# PSU_GainStage.net
KiCad netlist of a schematic drawn in EAGLE
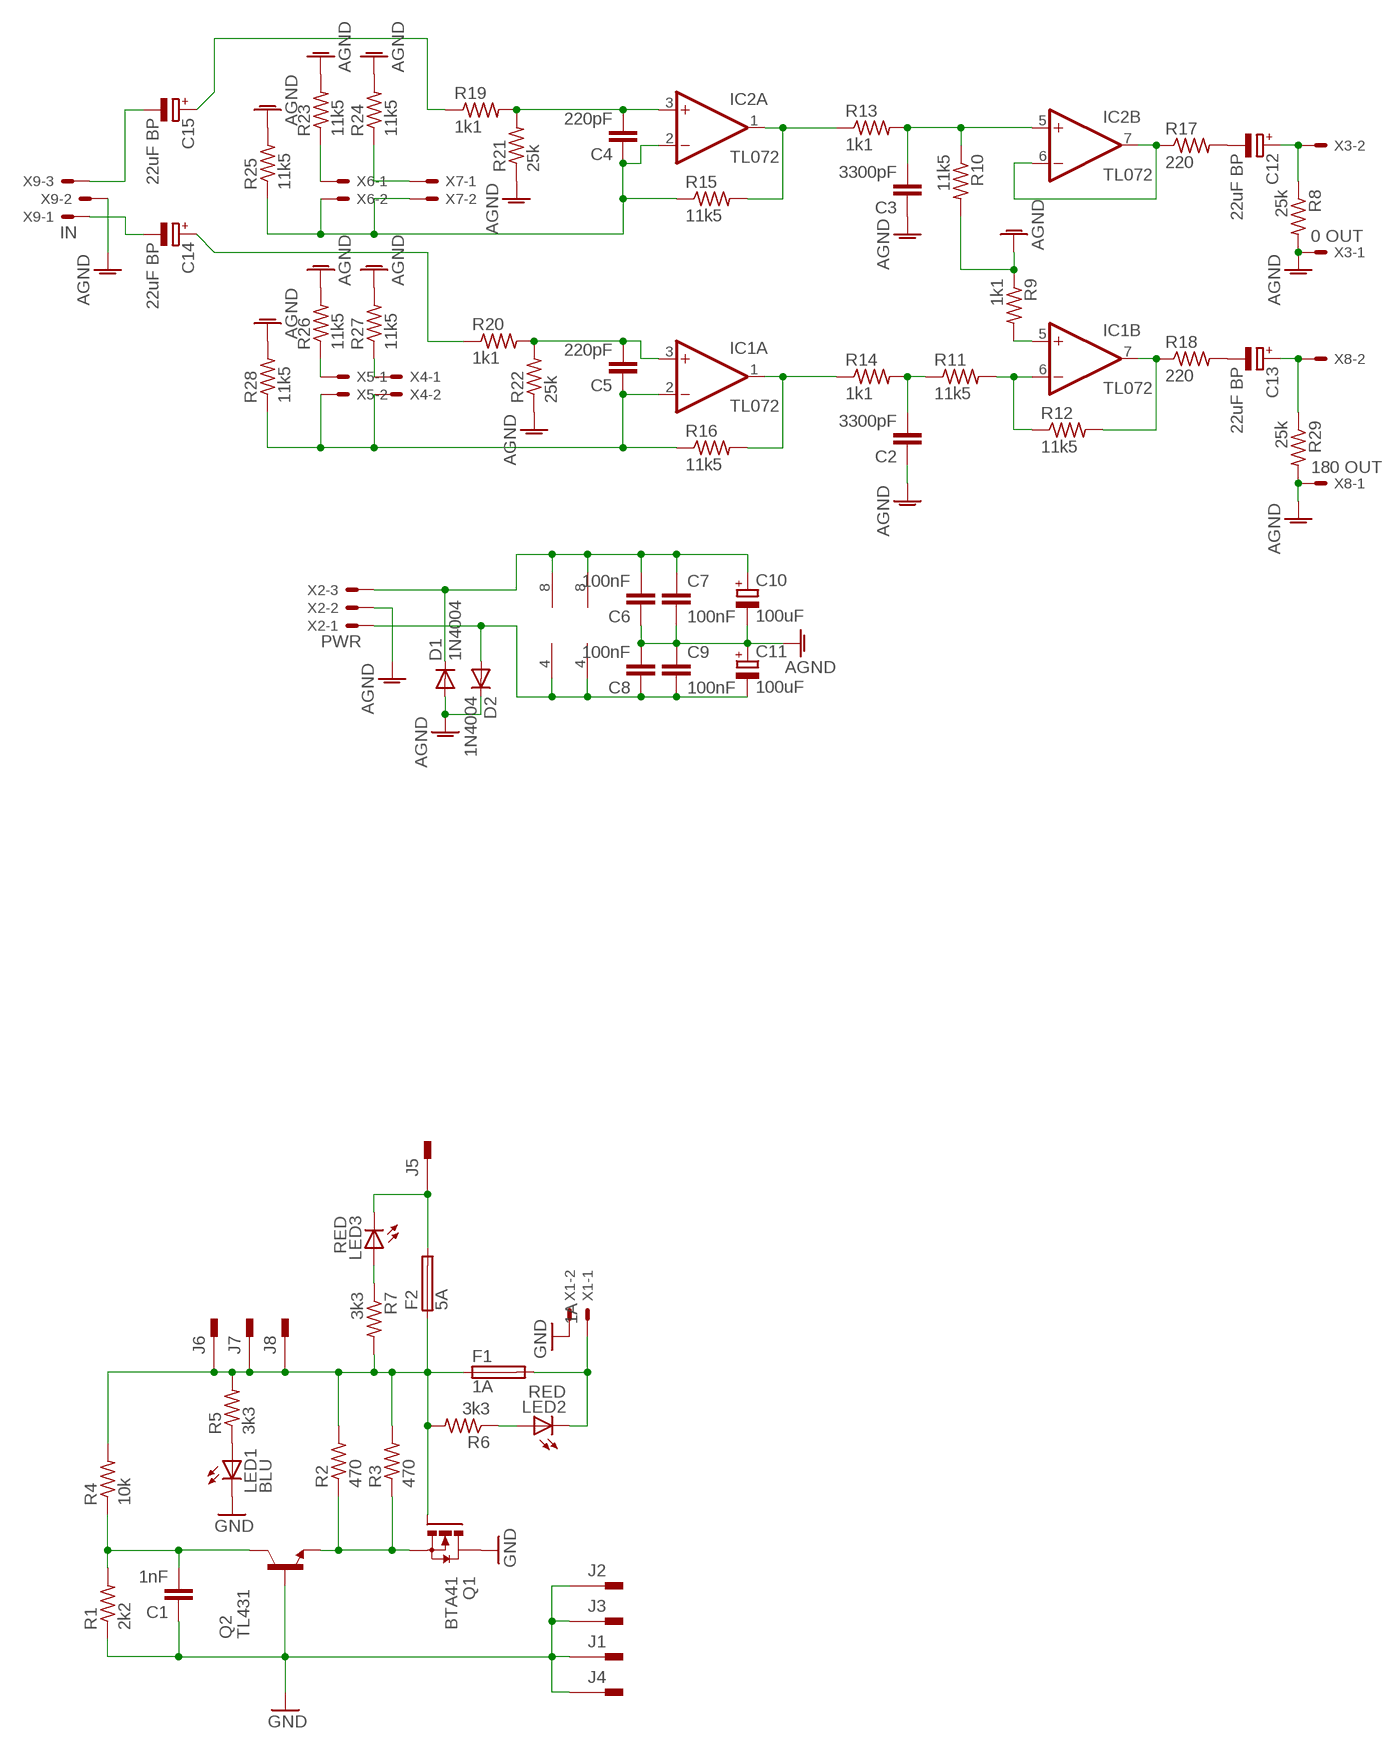
[diagram p0: schematic, sheet 1]

(export (version "E")
  (design (tool "Eeschema 10.0.6"))
  (components
    (comp (ref "C1")
      (value "1nF")
      (footprint "eagle-import:C050-035X075")
      (libsource (lib "eagle-import") (part "C-EU050-035X075"))
    )
    (comp (ref "C2")
      (value "3300pF")
      (footprint "eagle-import:C050-035X075")
      (libsource (lib "eagle-import") (part "C-EU050-035X075"))
    )
    (comp (ref "C3")
      (value "3300pF")
      (footprint "eagle-import:C050-035X075")
      (libsource (lib "eagle-import") (part "C-EU050-035X075"))
    )
    (comp (ref "C4")
      (value "220pF")
      (footprint "eagle-import:C050-035X075")
      (libsource (lib "eagle-import") (part "C-EU050-035X075"))
    )
    (comp (ref "C5")
      (value "220pF")
      (footprint "eagle-import:C050-035X075")
      (libsource (lib "eagle-import") (part "C-EU050-035X075"))
    )
    (comp (ref "C6")
      (value "100nF")
      (footprint "eagle-import:C1210")
      (libsource (lib "eagle-import") (part "C-EUC1210"))
    )
    (comp (ref "C7")
      (value "100nF")
      (footprint "eagle-import:C1210")
      (libsource (lib "eagle-import") (part "C-EUC1210"))
    )
    (comp (ref "C8")
      (value "100nF")
      (footprint "eagle-import:C1210")
      (libsource (lib "eagle-import") (part "C-EUC1210"))
    )
    (comp (ref "C9")
      (value "100nF")
      (footprint "eagle-import:C1210")
      (libsource (lib "eagle-import") (part "C-EUC1210"))
    )
    (comp (ref "C10")
      (value "100uF")
      (footprint "eagle-import:E5-8,5")
      (libsource (lib "eagle-import") (part "CPOL-EUE5-8.5"))
    )
    (comp (ref "C11")
      (value "100uF")
      (footprint "eagle-import:E5-8,5")
      (libsource (lib "eagle-import") (part "CPOL-EUE5-8.5"))
    )
    (comp (ref "C12")
      (value "22uF BP")
      (footprint "eagle-import:E3,5-10")
      (libsource (lib "eagle-import") (part "CPOL-EUE3.5-10"))
    )
    (comp (ref "C13")
      (value "22uF BP")
      (footprint "eagle-import:E3,5-10")
      (libsource (lib "eagle-import") (part "CPOL-EUE3.5-10"))
    )
    (comp (ref "C14")
      (value "22uF BP")
      (footprint "eagle-import:E3,5-10")
      (libsource (lib "eagle-import") (part "CPOL-EUE3.5-10"))
    )
    (comp (ref "C15")
      (value "22uF BP")
      (footprint "eagle-import:E3,5-10")
      (libsource (lib "eagle-import") (part "CPOL-EUE3.5-10"))
    )
    (comp (ref "D1")
      (value "1N4004")
      (footprint "eagle-import:DO41-10")
      (libsource (lib "eagle-import") (part "1N4004"))
    )
    (comp (ref "D2")
      (value "1N4004")
      (footprint "eagle-import:DO41-10")
      (libsource (lib "eagle-import") (part "1N4004"))
    )
    (comp (ref "F1")
      (value "1A")
      (footprint "eagle-import:TR5")
      (libsource (lib "eagle-import") (part "TR5"))
    )
    (comp (ref "F2")
      (value "5A")
      (footprint "eagle-import:TR5")
      (libsource (lib "eagle-import") (part "TR5"))
    )
    (comp (ref "IC1")
      (value "TL072")
      (footprint "eagle-import:DIL08")
      (libsource (lib "eagle-import") (part "1458NLM"))
    )
    (comp (ref "IC2")
      (value "TL072")
      (footprint "eagle-import:DIL08")
      (libsource (lib "eagle-import") (part "1458NLM"))
    )
    (comp (ref "J1")
      (value "PIN2F061.040")
      (footprint "eagle-import:F061.040")
      (libsource (lib "eagle-import") (part "PIN2F061.040"))
    )
    (comp (ref "J2")
      (value "PIN2F061.040")
      (footprint "eagle-import:F061.040")
      (libsource (lib "eagle-import") (part "PIN2F061.040"))
    )
    (comp (ref "J3")
      (value "PIN2F061.040")
      (footprint "eagle-import:F061.040")
      (libsource (lib "eagle-import") (part "PIN2F061.040"))
    )
    (comp (ref "J4")
      (value "PIN2F061.040")
      (footprint "eagle-import:F061.040")
      (libsource (lib "eagle-import") (part "PIN2F061.040"))
    )
    (comp (ref "J5")
      (value "PIN2F061.040")
      (footprint "eagle-import:F061.040")
      (libsource (lib "eagle-import") (part "PIN2F061.040"))
    )
    (comp (ref "J6")
      (value "PIN2F061.040")
      (footprint "eagle-import:F061.040")
      (libsource (lib "eagle-import") (part "PIN2F061.040"))
    )
    (comp (ref "J7")
      (value "PIN2F061.040")
      (footprint "eagle-import:F061.040")
      (libsource (lib "eagle-import") (part "PIN2F061.040"))
    )
    (comp (ref "J8")
      (value "PIN2F061.040")
      (footprint "eagle-import:F061.040")
      (libsource (lib "eagle-import") (part "PIN2F061.040"))
    )
    (comp (ref "LED1")
      (value "BLU")
      (footprint "eagle-import:LED5MM")
      (libsource (lib "eagle-import") (part "LED5MM"))
    )
    (comp (ref "LED2")
      (value "RED")
      (footprint "eagle-import:LED5MM")
      (libsource (lib "eagle-import") (part "LED5MM"))
    )
    (comp (ref "LED3")
      (value "RED")
      (footprint "eagle-import:LED5MM")
      (libsource (lib "eagle-import") (part "LED5MM"))
    )
    (comp (ref "Q1")
      (value "BTA41")
      (footprint "eagle-import:TO247BV")
      (libsource (lib "eagle-import") (part "IRFP240"))
    )
    (comp (ref "Q2")
      (value "TL431")
      (footprint "eagle-import:TO92-EBC")
      (libsource (lib "eagle-import") (part "BC449"))
    )
    (comp (ref "R1")
      (value "2k2")
      (footprint "eagle-import:0309_12")
      (libsource (lib "eagle-import") (part "R-US_0309/12"))
    )
    (comp (ref "R2")
      (value "470")
      (footprint "eagle-import:0411_15")
      (libsource (lib "eagle-import") (part "R-US_0411/15"))
    )
    (comp (ref "R3")
      (value "470")
      (footprint "eagle-import:0411_15")
      (libsource (lib "eagle-import") (part "R-US_0411/15"))
    )
    (comp (ref "R4")
      (value "10k")
      (footprint "eagle-import:0309_12")
      (libsource (lib "eagle-import") (part "R-US_0309/12"))
    )
    (comp (ref "R5")
      (value "3k3")
      (footprint "eagle-import:0309_12")
      (libsource (lib "eagle-import") (part "R-US_0309/12"))
    )
    (comp (ref "R6")
      (value "3k3")
      (footprint "eagle-import:0309_12")
      (libsource (lib "eagle-import") (part "R-US_0309/12"))
    )
    (comp (ref "R7")
      (value "3k3")
      (footprint "eagle-import:0309_12")
      (libsource (lib "eagle-import") (part "R-US_0309/12"))
    )
    (comp (ref "R8")
      (value "25k")
      (footprint "eagle-import:0309_12")
      (libsource (lib "eagle-import") (part "R-US_0309/12"))
    )
    (comp (ref "R9")
      (value "1k1")
      (footprint "eagle-import:0309_12")
      (libsource (lib "eagle-import") (part "R-US_0309/12"))
    )
    (comp (ref "R10")
      (value "11k5")
      (footprint "eagle-import:0309_12")
      (libsource (lib "eagle-import") (part "R-US_0309/12"))
    )
    (comp (ref "R11")
      (value "11k5")
      (footprint "eagle-import:0309_10")
      (libsource (lib "eagle-import") (part "R-US_0309/10"))
    )
    (comp (ref "R12")
      (value "11k5")
      (footprint "eagle-import:0309_10")
      (libsource (lib "eagle-import") (part "R-US_0309/10"))
    )
    (comp (ref "R13")
      (value "1k1")
      (footprint "eagle-import:0309_12")
      (libsource (lib "eagle-import") (part "R-US_0309/12"))
    )
    (comp (ref "R14")
      (value "1k1")
      (footprint "eagle-import:0309_12")
      (libsource (lib "eagle-import") (part "R-US_0309/12"))
    )
    (comp (ref "R15")
      (value "11k5")
      (footprint "eagle-import:0309_10")
      (libsource (lib "eagle-import") (part "R-US_0309/10"))
    )
    (comp (ref "R16")
      (value "11k5")
      (footprint "eagle-import:0309_10")
      (libsource (lib "eagle-import") (part "R-US_0309/10"))
    )
    (comp (ref "R17")
      (value "220")
      (footprint "eagle-import:0309_12")
      (libsource (lib "eagle-import") (part "R-US_0309/12"))
    )
    (comp (ref "R18")
      (value "220")
      (footprint "eagle-import:0309_10")
      (libsource (lib "eagle-import") (part "R-US_0309/10"))
    )
    (comp (ref "R19")
      (value "1k1")
      (footprint "eagle-import:0309_12")
      (libsource (lib "eagle-import") (part "R-US_0309/12"))
    )
    (comp (ref "R20")
      (value "1k1")
      (footprint "eagle-import:0309_10")
      (libsource (lib "eagle-import") (part "R-US_0309/10"))
    )
    (comp (ref "R21")
      (value "25k")
      (footprint "eagle-import:0309_10")
      (libsource (lib "eagle-import") (part "R-US_0309/10"))
    )
    (comp (ref "R22")
      (value "25k")
      (footprint "eagle-import:0309_10")
      (libsource (lib "eagle-import") (part "R-US_0309/10"))
    )
    (comp (ref "R23")
      (value "11k5")
      (footprint "eagle-import:0309_10")
      (libsource (lib "eagle-import") (part "R-US_0309/10"))
    )
    (comp (ref "R24")
      (value "11k5")
      (footprint "eagle-import:0309_10")
      (libsource (lib "eagle-import") (part "R-US_0309/10"))
    )
    (comp (ref "R25")
      (value "11k5")
      (footprint "eagle-import:0309_10")
      (libsource (lib "eagle-import") (part "R-US_0309/10"))
    )
    (comp (ref "R26")
      (value "11k5")
      (footprint "eagle-import:0309_10")
      (libsource (lib "eagle-import") (part "R-US_0309/10"))
    )
    (comp (ref "R27")
      (value "11k5")
      (footprint "eagle-import:0309_10")
      (libsource (lib "eagle-import") (part "R-US_0309/10"))
    )
    (comp (ref "R28")
      (value "11k5")
      (footprint "eagle-import:0309_10")
      (libsource (lib "eagle-import") (part "R-US_0309/10"))
    )
    (comp (ref "R29")
      (value "25k")
      (footprint "eagle-import:0309_12")
      (libsource (lib "eagle-import") (part "R-US_0309/12"))
    )
    (comp (ref "X1")
      (value "1A")
      (footprint "eagle-import:22-23-2021")
      (fields (field (name "MF") "MOLEX") (field (name "MPN") "22-23-2021"))
      (libsource (lib "eagle-import") (part "22-23-2021"))
    )
    (comp (ref "X2")
      (value "PWR")
      (footprint "eagle-import:22-23-2031")
      (fields (field (name "MF") "MOLEX") (field (name "MPN") "22-23-2031"))
      (libsource (lib "eagle-import") (part "22-23-2031"))
    )
    (comp (ref "X3")
      (value "0 OUT")
      (footprint "eagle-import:22-23-2021")
      (fields (field (name "MF") "MOLEX") (field (name "MPN") "22-23-2021"))
      (libsource (lib "eagle-import") (part "22-23-2021"))
    )
    (comp (ref "X4")
      (value "22-23-2021")
      (footprint "eagle-import:22-23-2021")
      (fields (field (name "MF") "MOLEX"))
      (libsource (lib "eagle-import") (part "22-23-2021"))
    )
    (comp (ref "X5")
      (value "22-23-2021")
      (footprint "eagle-import:22-23-2021")
      (fields (field (name "MF") "MOLEX"))
      (libsource (lib "eagle-import") (part "22-23-2021"))
    )
    (comp (ref "X6")
      (value "22-23-2021")
      (footprint "eagle-import:22-23-2021")
      (fields (field (name "MF") "MOLEX"))
      (libsource (lib "eagle-import") (part "22-23-2021"))
    )
    (comp (ref "X7")
      (value "22-23-2021")
      (footprint "eagle-import:22-23-2021")
      (fields (field (name "MF") "MOLEX"))
      (libsource (lib "eagle-import") (part "22-23-2021"))
    )
    (comp (ref "X8")
      (value "180 OUT")
      (footprint "eagle-import:22-23-2021")
      (fields (field (name "MF") "MOLEX") (field (name "MPN") "22-23-2021"))
      (libsource (lib "eagle-import") (part "22-23-2021"))
    )
    (comp (ref "X9")
      (value "IN")
      (footprint "eagle-import:22-23-2031")
      (fields (field (name "MF") "MOLEX") (field (name "MPN") "22-23-2031"))
      (libsource (lib "eagle-import") (part "22-23-2031"))
    )
  )
  (nets
    (net (code "1") (name "AGND") (class "Default")
      (node (ref "C10") (pin "-") (pinfunction "-_-") (pintype "passive"))
      (node (ref "C11") (pin "+") (pinfunction "+_+") (pintype "passive"))
      (node (ref "C2") (pin "1") (pinfunction "1_1") (pintype "passive"))
      (node (ref "C3") (pin "1") (pinfunction "1_1") (pintype "passive"))
      (node (ref "C6") (pin "1") (pinfunction "1_1") (pintype "passive"))
      (node (ref "C7") (pin "2") (pinfunction "2_2") (pintype "passive"))
      (node (ref "C8") (pin "2") (pinfunction "2_2") (pintype "passive"))
      (node (ref "C9") (pin "1") (pinfunction "1_1") (pintype "passive"))
      (node (ref "D1") (pin "A") (pinfunction "A_A") (pintype "passive"))
      (node (ref "D2") (pin "C") (pinfunction "C_C") (pintype "passive"))
      (node (ref "R10") (pin "2") (pinfunction "2_2") (pintype "passive"))
      (node (ref "R21") (pin "1") (pinfunction "1_1") (pintype "passive"))
      (node (ref "R22") (pin "1") (pinfunction "1_1") (pintype "passive"))
      (node (ref "R23") (pin "2") (pinfunction "2_2") (pintype "passive"))
      (node (ref "R24") (pin "2") (pinfunction "2_2") (pintype "passive"))
      (node (ref "R25") (pin "2") (pinfunction "2_2") (pintype "passive"))
      (node (ref "R26") (pin "2") (pinfunction "2_2") (pintype "passive"))
      (node (ref "R27") (pin "2") (pinfunction "2_2") (pintype "passive"))
      (node (ref "R28") (pin "2") (pinfunction "2_2") (pintype "passive"))
      (node (ref "R29") (pin "2") (pinfunction "2_2") (pintype "passive"))
      (node (ref "R8") (pin "2") (pinfunction "2_2") (pintype "passive"))
      (node (ref "R9") (pin "1") (pinfunction "1_1") (pintype "passive"))
      (node (ref "X2") (pin "2") (pinfunction "S_2") (pintype "passive"))
      (node (ref "X3") (pin "1") (pinfunction "S_1") (pintype "passive"))
      (node (ref "X8") (pin "1") (pinfunction "S_1") (pintype "passive"))
      (node (ref "X9") (pin "2") (pinfunction "S_2") (pintype "passive"))
    )
    (net (code "2") (name "GND") (class "Default")
      (node (ref "C1") (pin "1") (pinfunction "1_1") (pintype "passive"))
      (node (ref "J1") (pin "A1") (pinfunction "1_A1") (pintype "passive"))
      (node (ref "J1") (pin "A2") (pinfunction "1_A2") (pintype "passive"))
      (node (ref "J2") (pin "A1") (pinfunction "1_A1") (pintype "passive"))
      (node (ref "J2") (pin "A2") (pinfunction "1_A2") (pintype "passive"))
      (node (ref "J3") (pin "A1") (pinfunction "1_A1") (pintype "passive"))
      (node (ref "J3") (pin "A2") (pinfunction "1_A2") (pintype "passive"))
      (node (ref "J4") (pin "A1") (pinfunction "1_A1") (pintype "passive"))
      (node (ref "J4") (pin "A2") (pinfunction "1_A2") (pintype "passive"))
      (node (ref "LED1") (pin "K") (pinfunction "C_K") (pintype "passive"))
      (node (ref "Q1") (pin "D") (pinfunction "D_D") (pintype "passive"))
      (node (ref "Q2") (pin "B") (pinfunction "B_B") (pintype "passive"))
      (node (ref "R1") (pin "1") (pinfunction "1_1") (pintype "passive"))
      (node (ref "X1") (pin "2") (pinfunction "S_2") (pintype "passive"))
    )
    (net (code "3") (name "Net-(C1-Pad2)") (class "Default")
      (node (ref "C1") (pin "2") (pinfunction "2_2") (pintype "passive"))
      (node (ref "Q2") (pin "C") (pinfunction "C_C") (pintype "passive"))
      (node (ref "R1") (pin "2") (pinfunction "2_2") (pintype "passive"))
      (node (ref "R4") (pin "1") (pinfunction "1_1") (pintype "passive"))
    )
    (net (code "4") (name "Net-(C2-Pad2)") (class "Default")
      (node (ref "C2") (pin "2") (pinfunction "2_2") (pintype "passive"))
      (node (ref "R11") (pin "1") (pinfunction "1_1") (pintype "passive"))
      (node (ref "R14") (pin "2") (pinfunction "2_2") (pintype "passive"))
    )
    (net (code "5") (name "Net-(C12-Pad-)") (class "Default")
      (node (ref "C12") (pin "-") (pinfunction "-_-") (pintype "passive"))
      (node (ref "R17") (pin "2") (pinfunction "2_2") (pintype "passive"))
    )
    (net (code "6") (name "Net-(C13-Pad-)") (class "Default")
      (node (ref "C13") (pin "-") (pinfunction "-_-") (pintype "passive"))
      (node (ref "R18") (pin "2") (pinfunction "2_2") (pintype "passive"))
    )
    (net (code "7") (name "Net-(C14-Pad+)") (class "Default")
      (node (ref "C14") (pin "+") (pinfunction "+_+") (pintype "passive"))
      (node (ref "R20") (pin "1") (pinfunction "1_1") (pintype "passive"))
    )
    (net (code "8") (name "Net-(C15-Pad+)") (class "Default")
      (node (ref "C15") (pin "+") (pinfunction "+_+") (pintype "passive"))
      (node (ref "R19") (pin "1") (pinfunction "1_1") (pintype "passive"))
    )
    (net (code "9") (name "Net-(F1-Pad1)") (class "Default")
      (node (ref "F1") (pin "1") (pinfunction "1_1") (pintype "passive"))
      (node (ref "F2") (pin "1") (pinfunction "1_1") (pintype "passive"))
      (node (ref "J6") (pin "A1") (pinfunction "1_A1") (pintype "passive"))
      (node (ref "J6") (pin "A2") (pinfunction "1_A2") (pintype "passive"))
      (node (ref "J7") (pin "A1") (pinfunction "1_A1") (pintype "passive"))
      (node (ref "J7") (pin "A2") (pinfunction "1_A2") (pintype "passive"))
      (node (ref "J8") (pin "A1") (pinfunction "1_A1") (pintype "passive"))
      (node (ref "J8") (pin "A2") (pinfunction "1_A2") (pintype "passive"))
      (node (ref "Q1") (pin "G") (pinfunction "G_G") (pintype "passive"))
      (node (ref "R2") (pin "2") (pinfunction "2_2") (pintype "passive"))
      (node (ref "R3") (pin "2") (pinfunction "2_2") (pintype "passive"))
      (node (ref "R4") (pin "2") (pinfunction "2_2") (pintype "passive"))
      (node (ref "R5") (pin "2") (pinfunction "2_2") (pintype "passive"))
      (node (ref "R6") (pin "2") (pinfunction "2_2") (pintype "passive"))
      (node (ref "R7") (pin "2") (pinfunction "2_2") (pintype "passive"))
    )
    (net (code "10") (name "Net-(IC1A-+IN)") (class "Default")
      (node (ref "C5") (pin "2") (pinfunction "2_2") (pintype "passive"))
      (node (ref "IC1") (pin "3") (pinfunction "+IN_3") (pintype "input"))
      (node (ref "R20") (pin "2") (pinfunction "2_2") (pintype "passive"))
      (node (ref "R22") (pin "2") (pinfunction "2_2") (pintype "passive"))
    )
    (net (code "11") (name "Net-(IC1A--IN)") (class "Default")
      (node (ref "C5") (pin "1") (pinfunction "1_1") (pintype "passive"))
      (node (ref "IC1") (pin "2") (pinfunction "-IN_2") (pintype "input"))
      (node (ref "R16") (pin "1") (pinfunction "1_1") (pintype "passive"))
      (node (ref "R28") (pin "1") (pinfunction "1_1") (pintype "passive"))
      (node (ref "X4") (pin "2") (pinfunction "S_2") (pintype "passive"))
      (node (ref "X5") (pin "2") (pinfunction "S_2") (pintype "passive"))
    )
    (net (code "12") (name "Net-(IC1A-OUT)") (class "Default")
      (node (ref "IC1") (pin "1") (pinfunction "OUT_1") (pintype "output"))
      (node (ref "R14") (pin "1") (pinfunction "1_1") (pintype "passive"))
      (node (ref "R16") (pin "2") (pinfunction "2_2") (pintype "passive"))
    )
    (net (code "13") (name "Net-(IC1B-+IN)") (class "Default")
      (node (ref "IC1") (pin "5") (pinfunction "+IN_5") (pintype "input"))
      (node (ref "R9") (pin "2") (pinfunction "2_2") (pintype "passive"))
    )
    (net (code "14") (name "Net-(IC1B--IN)") (class "Default")
      (node (ref "IC1") (pin "6") (pinfunction "-IN_6") (pintype "input"))
      (node (ref "R11") (pin "2") (pinfunction "2_2") (pintype "passive"))
      (node (ref "R12") (pin "1") (pinfunction "1_1") (pintype "passive"))
    )
    (net (code "15") (name "Net-(IC1B-OUT)") (class "Default")
      (node (ref "IC1") (pin "7") (pinfunction "OUT_7") (pintype "output"))
      (node (ref "R12") (pin "2") (pinfunction "2_2") (pintype "passive"))
      (node (ref "R18") (pin "1") (pinfunction "1_1") (pintype "passive"))
    )
    (net (code "16") (name "Net-(IC1C-V+)") (class "Default")
      (node (ref "C10") (pin "+") (pinfunction "+_+") (pintype "passive"))
      (node (ref "C6") (pin "2") (pinfunction "2_2") (pintype "passive"))
      (node (ref "C7") (pin "1") (pinfunction "1_1") (pintype "passive"))
      (node (ref "D1") (pin "C") (pinfunction "C_C") (pintype "passive"))
      (node (ref "IC1") (pin "8") (pinfunction "V+_8") (pintype "power_in"))
      (node (ref "IC2") (pin "8") (pinfunction "V+_8") (pintype "power_in"))
      (node (ref "X2") (pin "3") (pinfunction "S_3") (pintype "passive"))
    )
    (net (code "17") (name "Net-(IC1C-V-)") (class "Default")
      (node (ref "C11") (pin "-") (pinfunction "-_-") (pintype "passive"))
      (node (ref "C8") (pin "1") (pinfunction "1_1") (pintype "passive"))
      (node (ref "C9") (pin "2") (pinfunction "2_2") (pintype "passive"))
      (node (ref "D2") (pin "A") (pinfunction "A_A") (pintype "passive"))
      (node (ref "IC1") (pin "4") (pinfunction "V-_4") (pintype "power_in"))
      (node (ref "IC2") (pin "4") (pinfunction "V-_4") (pintype "power_in"))
      (node (ref "X2") (pin "1") (pinfunction "S_1") (pintype "passive"))
    )
    (net (code "18") (name "Net-(IC2A-+IN)") (class "Default")
      (node (ref "C4") (pin "2") (pinfunction "2_2") (pintype "passive"))
      (node (ref "IC2") (pin "3") (pinfunction "+IN_3") (pintype "input"))
      (node (ref "R19") (pin "2") (pinfunction "2_2") (pintype "passive"))
      (node (ref "R21") (pin "2") (pinfunction "2_2") (pintype "passive"))
    )
    (net (code "19") (name "Net-(IC2A--IN)") (class "Default")
      (node (ref "C4") (pin "1") (pinfunction "1_1") (pintype "passive"))
      (node (ref "IC2") (pin "2") (pinfunction "-IN_2") (pintype "input"))
      (node (ref "R15") (pin "1") (pinfunction "1_1") (pintype "passive"))
      (node (ref "R25") (pin "1") (pinfunction "1_1") (pintype "passive"))
      (node (ref "X6") (pin "2") (pinfunction "S_2") (pintype "passive"))
      (node (ref "X7") (pin "2") (pinfunction "S_2") (pintype "passive"))
    )
    (net (code "20") (name "Net-(IC2A-OUT)") (class "Default")
      (node (ref "IC2") (pin "1") (pinfunction "OUT_1") (pintype "output"))
      (node (ref "R13") (pin "1") (pinfunction "1_1") (pintype "passive"))
      (node (ref "R15") (pin "2") (pinfunction "2_2") (pintype "passive"))
    )
    (net (code "21") (name "Net-(IC2B-+IN)") (class "Default")
      (node (ref "C3") (pin "2") (pinfunction "2_2") (pintype "passive"))
      (node (ref "IC2") (pin "5") (pinfunction "+IN_5") (pintype "input"))
      (node (ref "R10") (pin "1") (pinfunction "1_1") (pintype "passive"))
      (node (ref "R13") (pin "2") (pinfunction "2_2") (pintype "passive"))
    )
    (net (code "22") (name "Net-(IC2B--IN)") (class "Default")
      (node (ref "IC2") (pin "6") (pinfunction "-IN_6") (pintype "input"))
      (node (ref "IC2") (pin "7") (pinfunction "OUT_7") (pintype "output"))
      (node (ref "R17") (pin "1") (pinfunction "1_1") (pintype "passive"))
    )
    (net (code "23") (name "Net-(LED1-PadA)") (class "Default")
      (node (ref "LED1") (pin "A") (pinfunction "A_A") (pintype "passive"))
      (node (ref "R5") (pin "1") (pinfunction "1_1") (pintype "passive"))
    )
    (net (code "24") (name "Net-(LED2-C)") (class "Default")
      (node (ref "F1") (pin "2") (pinfunction "2_2") (pintype "passive"))
      (node (ref "LED2") (pin "K") (pinfunction "C_K") (pintype "passive"))
      (node (ref "X1") (pin "1") (pinfunction "S_1") (pintype "passive"))
    )
    (net (code "25") (name "Net-(LED2-PadA)") (class "Default")
      (node (ref "LED2") (pin "A") (pinfunction "A_A") (pintype "passive"))
      (node (ref "R6") (pin "1") (pinfunction "1_1") (pintype "passive"))
    )
    (net (code "26") (name "Net-(LED3-C)") (class "Default")
      (node (ref "F2") (pin "2") (pinfunction "2_2") (pintype "passive"))
      (node (ref "J5") (pin "A1") (pinfunction "1_A1") (pintype "passive"))
      (node (ref "J5") (pin "A2") (pinfunction "1_A2") (pintype "passive"))
      (node (ref "LED3") (pin "K") (pinfunction "C_K") (pintype "passive"))
    )
    (net (code "27") (name "Net-(LED3-PadA)") (class "Default")
      (node (ref "LED3") (pin "A") (pinfunction "A_A") (pintype "passive"))
      (node (ref "R7") (pin "1") (pinfunction "1_1") (pintype "passive"))
    )
    (net (code "28") (name "Net-(Q1-PadS)") (class "Default")
      (node (ref "Q1") (pin "S") (pinfunction "S_S") (pintype "passive"))
      (node (ref "Q2") (pin "E") (pinfunction "E_E") (pintype "passive"))
      (node (ref "R2") (pin "1") (pinfunction "1_1") (pintype "passive"))
      (node (ref "R3") (pin "1") (pinfunction "1_1") (pintype "passive"))
    )
    (net (code "29") (name "Net-(X3B-S)") (class "Default")
      (node (ref "C12") (pin "+") (pinfunction "+_+") (pintype "passive"))
      (node (ref "R8") (pin "1") (pinfunction "1_1") (pintype "passive"))
      (node (ref "X3") (pin "2") (pinfunction "S_2") (pintype "passive"))
    )
    (net (code "30") (name "Net-(X4A-S)") (class "Default")
      (node (ref "R27") (pin "1") (pinfunction "1_1") (pintype "passive"))
      (node (ref "X4") (pin "1") (pinfunction "S_1") (pintype "passive"))
    )
    (net (code "31") (name "Net-(X5A-S)") (class "Default")
      (node (ref "R26") (pin "1") (pinfunction "1_1") (pintype "passive"))
      (node (ref "X5") (pin "1") (pinfunction "S_1") (pintype "passive"))
    )
    (net (code "32") (name "Net-(X6A-S)") (class "Default")
      (node (ref "R23") (pin "1") (pinfunction "1_1") (pintype "passive"))
      (node (ref "X6") (pin "1") (pinfunction "S_1") (pintype "passive"))
    )
    (net (code "33") (name "Net-(X7A-S)") (class "Default")
      (node (ref "R24") (pin "1") (pinfunction "1_1") (pintype "passive"))
      (node (ref "X7") (pin "1") (pinfunction "S_1") (pintype "passive"))
    )
    (net (code "34") (name "Net-(X8B-S)") (class "Default")
      (node (ref "C13") (pin "+") (pinfunction "+_+") (pintype "passive"))
      (node (ref "R29") (pin "1") (pinfunction "1_1") (pintype "passive"))
      (node (ref "X8") (pin "2") (pinfunction "S_2") (pintype "passive"))
    )
    (net (code "35") (name "Net-(X9A-S)") (class "Default")
      (node (ref "C14") (pin "-") (pinfunction "-_-") (pintype "passive"))
      (node (ref "X9") (pin "1") (pinfunction "S_1") (pintype "passive"))
    )
    (net (code "36") (name "Net-(X9C-S)") (class "Default")
      (node (ref "C15") (pin "-") (pinfunction "-_-") (pintype "passive"))
      (node (ref "X9") (pin "3") (pinfunction "S_3") (pintype "passive"))
    )
  )
)
